# HackmodWear.net
KiCad netlist of a schematic drawn in EAGLE
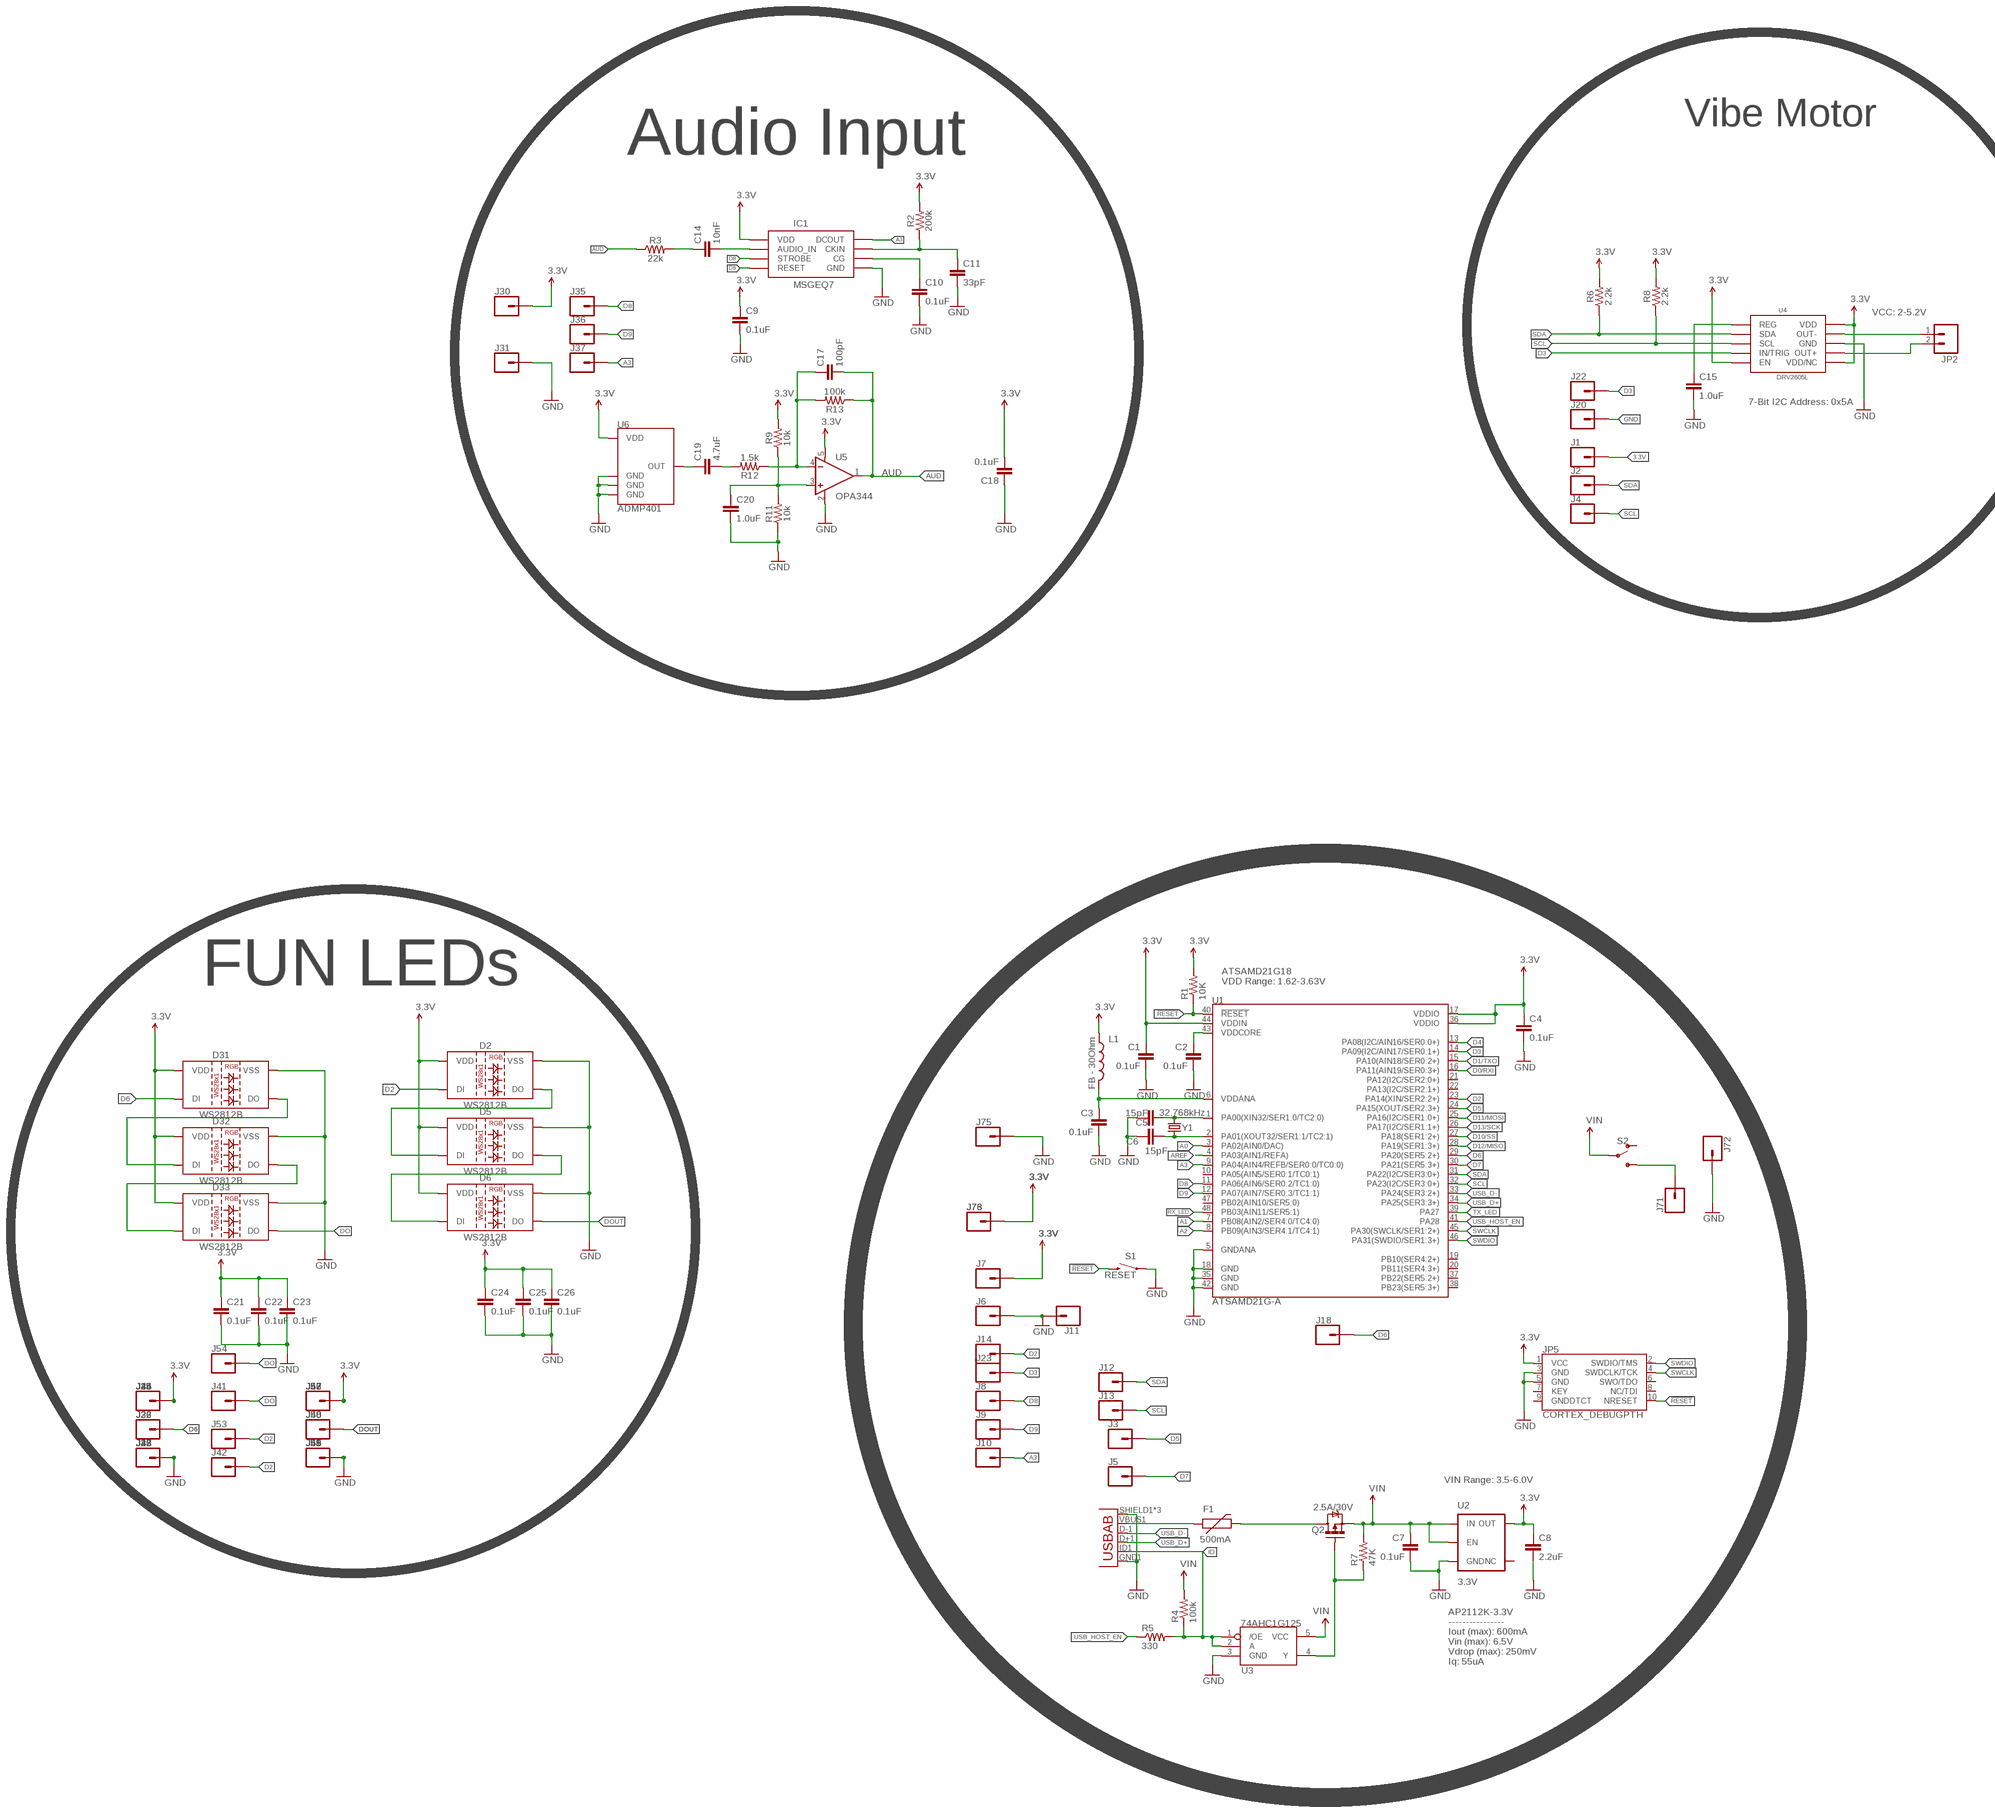
[diagram p0: schematic, sheet 1, part 1 of 3]
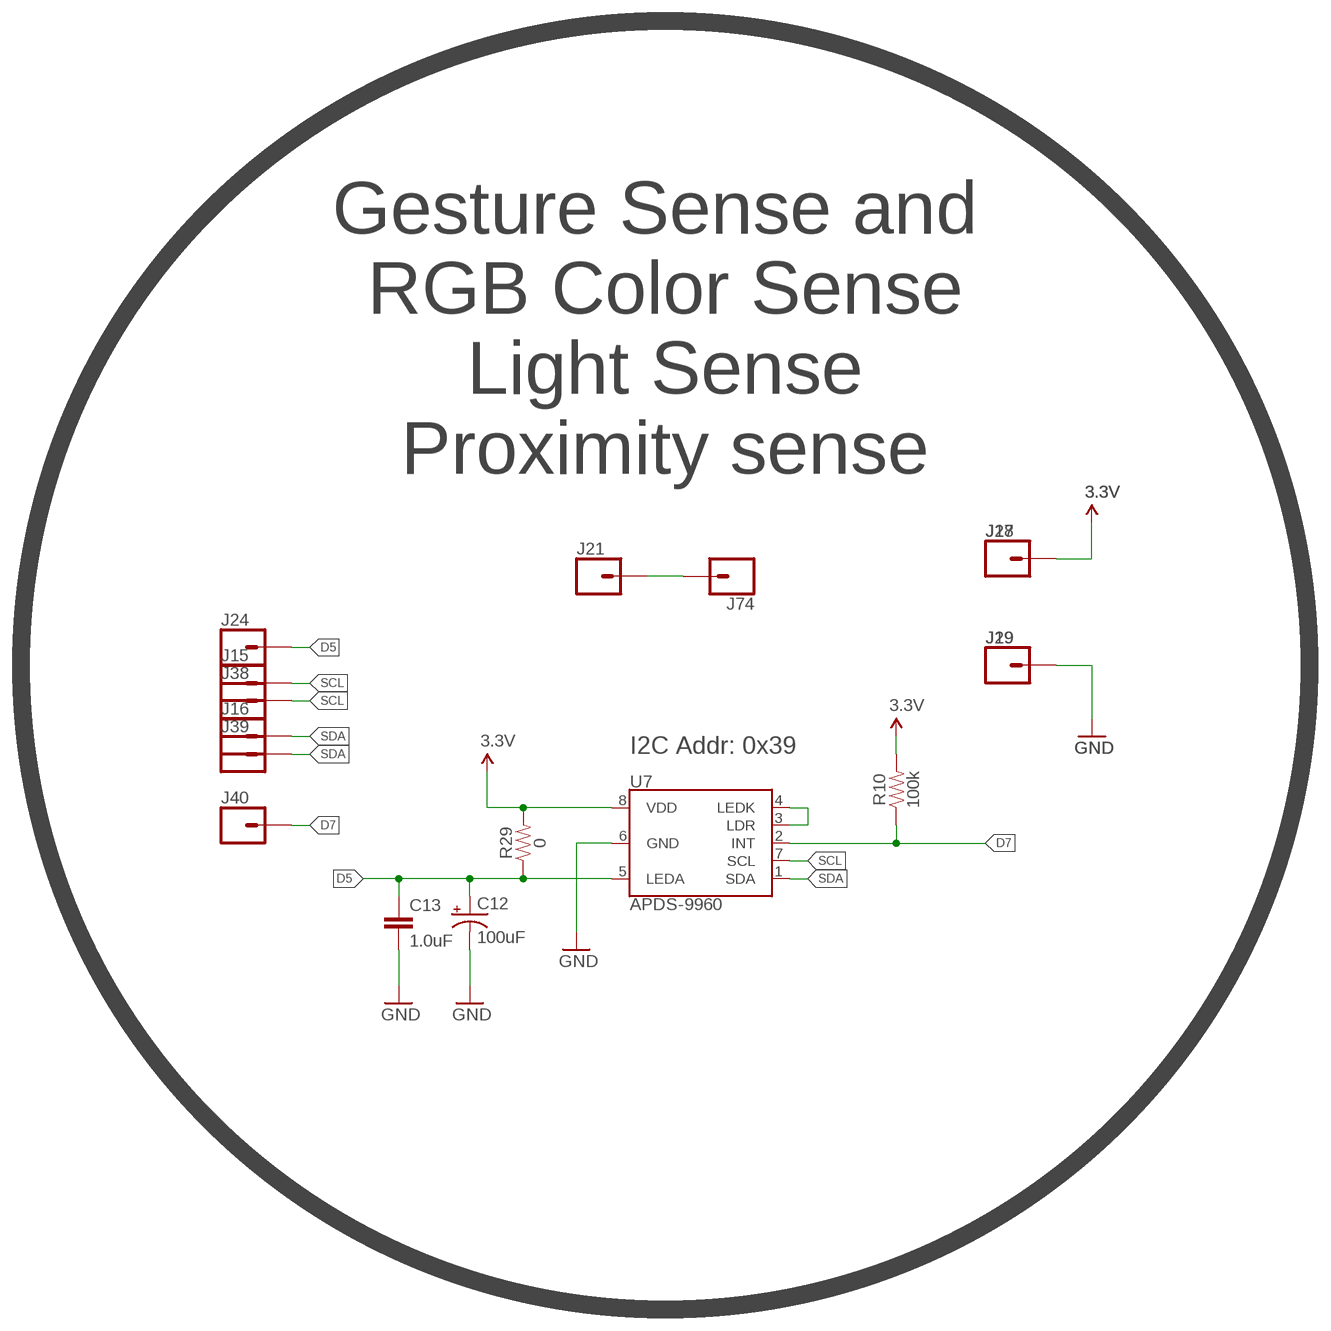
[diagram p1: schematic, sheet 1, part 2 of 3]
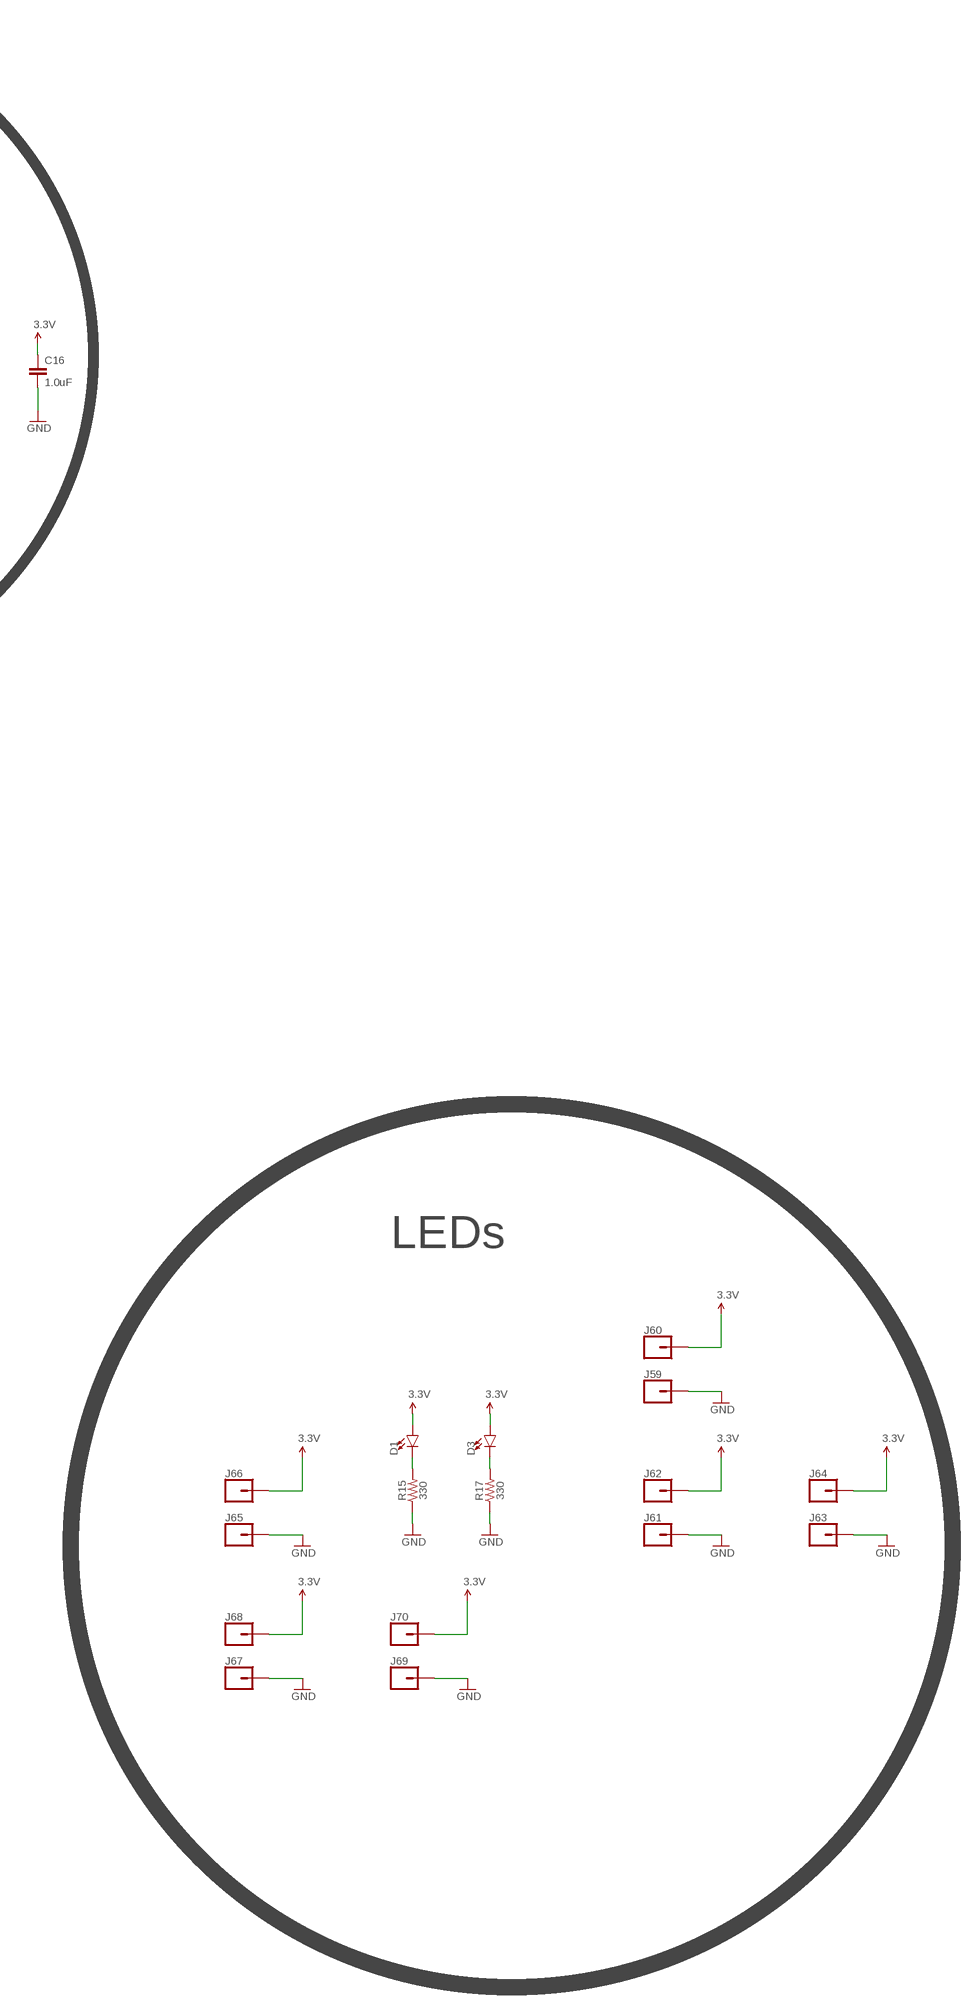
[diagram p2: schematic, sheet 1, part 3 of 3]

(export (version "E")
  (design (tool "Eeschema 10.0.6"))
  (components
    (comp (ref "C1")
      (value "0.1uF")
      (footprint "eagle-import:0603")
      (libsource (lib "eagle-import") (part "0.1UF-0603-25V-(+80/-20%)"))
    )
    (comp (ref "C2")
      (value "0.1uF")
      (footprint "eagle-import:0603")
      (libsource (lib "eagle-import") (part "0.1UF-0603-25V-(+80/-20%)"))
    )
    (comp (ref "C3")
      (value "0.1uF")
      (footprint "eagle-import:0603")
      (libsource (lib "eagle-import") (part "0.1UF-0603-25V-(+80/-20%)"))
    )
    (comp (ref "C4")
      (value "0.1uF")
      (footprint "eagle-import:0603")
      (libsource (lib "eagle-import") (part "0.1UF-0603-25V-(+80/-20%)"))
    )
    (comp (ref "C5")
      (value "15pF")
      (footprint "eagle-import:0603")
      (libsource (lib "eagle-import") (part "15PF-0603-50V-5%"))
    )
    (comp (ref "C6")
      (value "15pF")
      (footprint "eagle-import:0603")
      (libsource (lib "eagle-import") (part "15PF-0603-50V-5%"))
    )
    (comp (ref "C7")
      (value "0.1uF")
      (footprint "eagle-import:0603")
      (libsource (lib "eagle-import") (part "0.1UF-0603-25V-(+80/-20%)"))
    )
    (comp (ref "C8")
      (value "2.2uF")
      (footprint "eagle-import:0603-CAP")
      (libsource (lib "eagle-import") (part "2.2UF-10V-20%(0603)"))
    )
    (comp (ref "C9")
      (value "0.1uF")
      (footprint "eagle-import:0603")
      (libsource (lib "eagle-import") (part "0.1UF-0603-25V-(+80/-20%)"))
    )
    (comp (ref "C10")
      (value "0.1uF")
      (footprint "eagle-import:0603")
      (libsource (lib "eagle-import") (part "0.1UF-0603-25V-(+80/-20%)"))
    )
    (comp (ref "C11")
      (value "33pF")
      (footprint "eagle-import:0603")
      (libsource (lib "eagle-import") (part "33PF-0603-50V-5%"))
    )
    (comp (ref "C12")
      (value "100uF")
      (footprint "eagle-import:EIA7343")
      (libsource (lib "eagle-import") (part "100UF-POLAR-EIA7343-10V-10%(TANT)"))
    )
    (comp (ref "C13")
      (value "1.0uF")
      (footprint "eagle-import:0603")
      (libsource (lib "eagle-import") (part "1.0UF-0603-16V-10%"))
    )
    (comp (ref "C14")
      (value "10nF")
      (footprint "eagle-import:0603")
      (libsource (lib "eagle-import") (part "10NF-0603-50V-10%"))
    )
    (comp (ref "C15")
      (value "1.0uF")
      (footprint "eagle-import:0402-CAP")
      (libsource (lib "eagle-import") (part "1.0UF-16V-10%(0402)"))
    )
    (comp (ref "C16")
      (value "1.0uF")
      (footprint "eagle-import:0402-CAP")
      (libsource (lib "eagle-import") (part "1.0UF-16V-10%(0402)"))
    )
    (comp (ref "C17")
      (value "100pF")
      (footprint "eagle-import:0603")
      (libsource (lib "eagle-import") (part "100PF-0603-50V-5%"))
    )
    (comp (ref "C18")
      (value "0.1uF")
      (footprint "eagle-import:0603")
      (libsource (lib "eagle-import") (part "0.1UF-0603-25V-(+80/-20%)"))
    )
    (comp (ref "C19")
      (value "4.7uF")
      (footprint "eagle-import:0603")
      (libsource (lib "eagle-import") (part "4.7UF0603"))
    )
    (comp (ref "C20")
      (value "1.0uF")
      (footprint "eagle-import:0603")
      (libsource (lib "eagle-import") (part "1.0UF-0603-16V-10%"))
    )
    (comp (ref "C21")
      (value "0.1uF")
      (footprint "eagle-import:0603")
      (libsource (lib "eagle-import") (part "0.1UF-0603-25V-(+80/-20%)"))
    )
    (comp (ref "C22")
      (value "0.1uF")
      (footprint "eagle-import:0603")
      (libsource (lib "eagle-import") (part "0.1UF-0603-25V-(+80/-20%)"))
    )
    (comp (ref "C23")
      (value "0.1uF")
      (footprint "eagle-import:0603")
      (libsource (lib "eagle-import") (part "0.1UF-0603-25V-(+80/-20%)"))
    )
    (comp (ref "C24")
      (value "0.1uF")
      (footprint "eagle-import:0603")
      (libsource (lib "eagle-import") (part "0.1UF-0603-25V-(+80/-20%)"))
    )
    (comp (ref "C25")
      (value "0.1uF")
      (footprint "eagle-import:0603")
      (libsource (lib "eagle-import") (part "0.1UF-0603-25V-(+80/-20%)"))
    )
    (comp (ref "C26")
      (value "0.1uF")
      (footprint "eagle-import:0603")
      (libsource (lib "eagle-import") (part "0.1UF-0603-25V-(+80/-20%)"))
    )
    (comp (ref "D1")
      (value "LED1206")
      (footprint "eagle-import:LED-1206")
      (libsource (lib "eagle-import") (part "LED1206"))
    )
    (comp (ref "D2")
      (value "WS2812B")
      (footprint "eagle-import:WS2812B")
      (libsource (lib "eagle-import") (part "WS2812B"))
    )
    (comp (ref "D3")
      (value "LED1206")
      (footprint "eagle-import:LED-1206")
      (libsource (lib "eagle-import") (part "LED1206"))
    )
    (comp (ref "D5")
      (value "WS2812B")
      (footprint "eagle-import:WS2812B")
      (libsource (lib "eagle-import") (part "WS2812B"))
    )
    (comp (ref "D6")
      (value "WS2812B")
      (footprint "eagle-import:WS2812B")
      (libsource (lib "eagle-import") (part "WS2812B"))
    )
    (comp (ref "D31")
      (value "WS2812B")
      (footprint "eagle-import:WS2812B")
      (libsource (lib "eagle-import") (part "WS2812B"))
    )
    (comp (ref "D32")
      (value "WS2812B")
      (footprint "eagle-import:WS2812B")
      (libsource (lib "eagle-import") (part "WS2812B"))
    )
    (comp (ref "D33")
      (value "WS2812B")
      (footprint "eagle-import:WS2812B")
      (libsource (lib "eagle-import") (part "WS2812B"))
    )
    (comp (ref "F1")
      (value "500mA")
      (footprint "eagle-import:PTC-1206")
      (libsource (lib "eagle-import") (part "PTCSMD"))
    )
    (comp (ref "IC1")
      (value "MSGEQ7N")
      (footprint "eagle-import:SO08")
      (libsource (lib "eagle-import") (part "MSGEQ7SOIC"))
    )
    (comp (ref "J1")
      (value "CONN_01")
      (footprint "eagle-import:1X01")
      (libsource (lib "eagle-import") (part "CONN_01"))
    )
    (comp (ref "J2")
      (value "CONN_01")
      (footprint "eagle-import:1X01")
      (libsource (lib "eagle-import") (part "CONN_01"))
    )
    (comp (ref "J3")
      (value "CONN_01")
      (footprint "eagle-import:1X01")
      (libsource (lib "eagle-import") (part "CONN_01"))
    )
    (comp (ref "J4")
      (value "CONN_01")
      (footprint "eagle-import:1X01")
      (libsource (lib "eagle-import") (part "CONN_01"))
    )
    (comp (ref "J5")
      (value "CONN_01")
      (footprint "eagle-import:1X01")
      (libsource (lib "eagle-import") (part "CONN_01"))
    )
    (comp (ref "J6")
      (value "CONN_01")
      (footprint "eagle-import:1X01")
      (libsource (lib "eagle-import") (part "CONN_01"))
    )
    (comp (ref "J7")
      (value "CONN_01")
      (footprint "eagle-import:1X01")
      (libsource (lib "eagle-import") (part "CONN_01"))
    )
    (comp (ref "J8")
      (value "CONN_01")
      (footprint "eagle-import:1X01")
      (libsource (lib "eagle-import") (part "CONN_01"))
    )
    (comp (ref "J9")
      (value "CONN_01")
      (footprint "eagle-import:1X01")
      (libsource (lib "eagle-import") (part "CONN_01"))
    )
    (comp (ref "J10")
      (value "CONN_01")
      (footprint "eagle-import:1X01")
      (libsource (lib "eagle-import") (part "CONN_01"))
    )
    (comp (ref "J11")
      (value "CONN_01")
      (footprint "eagle-import:1X01")
      (libsource (lib "eagle-import") (part "CONN_01"))
    )
    (comp (ref "J12")
      (value "CONN_01")
      (footprint "eagle-import:1X01")
      (libsource (lib "eagle-import") (part "CONN_01"))
    )
    (comp (ref "J13")
      (value "CONN_01")
      (footprint "eagle-import:1X01")
      (libsource (lib "eagle-import") (part "CONN_01"))
    )
    (comp (ref "J14")
      (value "CONN_01")
      (footprint "eagle-import:1X01")
      (libsource (lib "eagle-import") (part "CONN_01"))
    )
    (comp (ref "J15")
      (value "CONN_01")
      (footprint "eagle-import:1X01")
      (libsource (lib "eagle-import") (part "CONN_01"))
    )
    (comp (ref "J16")
      (value "CONN_01")
      (footprint "eagle-import:1X01")
      (libsource (lib "eagle-import") (part "CONN_01"))
    )
    (comp (ref "J17")
      (value "CONN_01")
      (footprint "eagle-import:1X01")
      (libsource (lib "eagle-import") (part "CONN_01"))
    )
    (comp (ref "J18")
      (value "CONN_01")
      (footprint "eagle-import:1X01")
      (libsource (lib "eagle-import") (part "CONN_01"))
    )
    (comp (ref "J19")
      (value "CONN_01")
      (footprint "eagle-import:1X01")
      (libsource (lib "eagle-import") (part "CONN_01"))
    )
    (comp (ref "J20")
      (value "CONN_01")
      (footprint "eagle-import:1X01")
      (libsource (lib "eagle-import") (part "CONN_01"))
    )
    (comp (ref "J21")
      (value "CONN_01")
      (footprint "eagle-import:1X01")
      (libsource (lib "eagle-import") (part "CONN_01"))
    )
    (comp (ref "J22")
      (value "CONN_01")
      (footprint "eagle-import:1X01")
      (libsource (lib "eagle-import") (part "CONN_01"))
    )
    (comp (ref "J23")
      (value "CONN_01")
      (footprint "eagle-import:1X01")
      (libsource (lib "eagle-import") (part "CONN_01"))
    )
    (comp (ref "J24")
      (value "CONN_01")
      (footprint "eagle-import:1X01")
      (libsource (lib "eagle-import") (part "CONN_01"))
    )
    (comp (ref "J25")
      (value "CONN_01")
      (footprint "eagle-import:1X01")
      (libsource (lib "eagle-import") (part "CONN_01"))
    )
    (comp (ref "J26")
      (value "CONN_01")
      (footprint "eagle-import:1X01")
      (libsource (lib "eagle-import") (part "CONN_01"))
    )
    (comp (ref "J27")
      (value "CONN_01")
      (footprint "eagle-import:1X01")
      (libsource (lib "eagle-import") (part "CONN_01"))
    )
    (comp (ref "J28")
      (value "CONN_01")
      (footprint "eagle-import:1X01")
      (libsource (lib "eagle-import") (part "CONN_01"))
    )
    (comp (ref "J29")
      (value "CONN_01")
      (footprint "eagle-import:1X01")
      (libsource (lib "eagle-import") (part "CONN_01"))
    )
    (comp (ref "J30")
      (value "CONN_01")
      (footprint "eagle-import:1X01")
      (libsource (lib "eagle-import") (part "CONN_01"))
    )
    (comp (ref "J31")
      (value "CONN_01")
      (footprint "eagle-import:1X01")
      (libsource (lib "eagle-import") (part "CONN_01"))
    )
    (comp (ref "J32")
      (value "CONN_01")
      (footprint "eagle-import:1X01")
      (libsource (lib "eagle-import") (part "CONN_01"))
    )
    (comp (ref "J33")
      (value "CONN_01")
      (footprint "eagle-import:1X01")
      (libsource (lib "eagle-import") (part "CONN_01"))
    )
    (comp (ref "J34")
      (value "CONN_01")
      (footprint "eagle-import:1X01")
      (libsource (lib "eagle-import") (part "CONN_01"))
    )
    (comp (ref "J35")
      (value "CONN_01")
      (footprint "eagle-import:1X01")
      (libsource (lib "eagle-import") (part "CONN_01"))
    )
    (comp (ref "J36")
      (value "CONN_01")
      (footprint "eagle-import:1X01")
      (libsource (lib "eagle-import") (part "CONN_01"))
    )
    (comp (ref "J37")
      (value "CONN_01")
      (footprint "eagle-import:1X01")
      (libsource (lib "eagle-import") (part "CONN_01"))
    )
    (comp (ref "J38")
      (value "CONN_01")
      (footprint "eagle-import:1X01")
      (libsource (lib "eagle-import") (part "CONN_01"))
    )
    (comp (ref "J39")
      (value "CONN_01")
      (footprint "eagle-import:1X01")
      (libsource (lib "eagle-import") (part "CONN_01"))
    )
    (comp (ref "J40")
      (value "CONN_01")
      (footprint "eagle-import:1X01")
      (libsource (lib "eagle-import") (part "CONN_01"))
    )
    (comp (ref "J41")
      (value "CONN_01")
      (footprint "eagle-import:1X01")
      (libsource (lib "eagle-import") (part "CONN_01"))
    )
    (comp (ref "J42")
      (value "CONN_01")
      (footprint "eagle-import:1X01")
      (libsource (lib "eagle-import") (part "CONN_01"))
    )
    (comp (ref "J43")
      (value "CONN_01")
      (footprint "eagle-import:1X01")
      (libsource (lib "eagle-import") (part "CONN_01"))
    )
    (comp (ref "J44")
      (value "CONN_01")
      (footprint "eagle-import:1X01")
      (libsource (lib "eagle-import") (part "CONN_01"))
    )
    (comp (ref "J45")
      (value "CONN_01")
      (footprint "eagle-import:1X01")
      (libsource (lib "eagle-import") (part "CONN_01"))
    )
    (comp (ref "J46")
      (value "CONN_01")
      (footprint "eagle-import:1X01")
      (libsource (lib "eagle-import") (part "CONN_01"))
    )
    (comp (ref "J47")
      (value "CONN_01")
      (footprint "eagle-import:1X01")
      (libsource (lib "eagle-import") (part "CONN_01"))
    )
    (comp (ref "J48")
      (value "CONN_01")
      (footprint "eagle-import:1X01")
      (libsource (lib "eagle-import") (part "CONN_01"))
    )
    (comp (ref "J49")
      (value "CONN_01")
      (footprint "eagle-import:1X01")
      (libsource (lib "eagle-import") (part "CONN_01"))
    )
    (comp (ref "J50")
      (value "CONN_01")
      (footprint "eagle-import:1X01")
      (libsource (lib "eagle-import") (part "CONN_01"))
    )
    (comp (ref "J51")
      (value "CONN_01")
      (footprint "eagle-import:1X01")
      (libsource (lib "eagle-import") (part "CONN_01"))
    )
    (comp (ref "J52")
      (value "CONN_01")
      (footprint "eagle-import:1X01")
      (libsource (lib "eagle-import") (part "CONN_01"))
    )
    (comp (ref "J53")
      (value "CONN_01")
      (footprint "eagle-import:1X01")
      (libsource (lib "eagle-import") (part "CONN_01"))
    )
    (comp (ref "J54")
      (value "CONN_01")
      (footprint "eagle-import:1X01")
      (libsource (lib "eagle-import") (part "CONN_01"))
    )
    (comp (ref "J55")
      (value "CONN_01")
      (footprint "eagle-import:1X01")
      (libsource (lib "eagle-import") (part "CONN_01"))
    )
    (comp (ref "J56")
      (value "CONN_01")
      (footprint "eagle-import:1X01")
      (libsource (lib "eagle-import") (part "CONN_01"))
    )
    (comp (ref "J57")
      (value "CONN_01")
      (footprint "eagle-import:1X01")
      (libsource (lib "eagle-import") (part "CONN_01"))
    )
    (comp (ref "J58")
      (value "CONN_01")
      (footprint "eagle-import:1X01")
      (libsource (lib "eagle-import") (part "CONN_01"))
    )
    (comp (ref "J59")
      (value "CONN_01")
      (footprint "eagle-import:1X01")
      (libsource (lib "eagle-import") (part "CONN_01"))
    )
    (comp (ref "J60")
      (value "CONN_01")
      (footprint "eagle-import:1X01")
      (libsource (lib "eagle-import") (part "CONN_01"))
    )
    (comp (ref "J61")
      (value "CONN_01")
      (footprint "eagle-import:1X01")
      (libsource (lib "eagle-import") (part "CONN_01"))
    )
    (comp (ref "J62")
      (value "CONN_01")
      (footprint "eagle-import:1X01")
      (libsource (lib "eagle-import") (part "CONN_01"))
    )
    (comp (ref "J63")
      (value "CONN_01")
      (footprint "eagle-import:1X01")
      (libsource (lib "eagle-import") (part "CONN_01"))
    )
    (comp (ref "J64")
      (value "CONN_01")
      (footprint "eagle-import:1X01")
      (libsource (lib "eagle-import") (part "CONN_01"))
    )
    (comp (ref "J65")
      (value "CONN_01")
      (footprint "eagle-import:1X01")
      (libsource (lib "eagle-import") (part "CONN_01"))
    )
    (comp (ref "J66")
      (value "CONN_01")
      (footprint "eagle-import:1X01")
      (libsource (lib "eagle-import") (part "CONN_01"))
    )
    (comp (ref "J67")
      (value "CONN_01")
      (footprint "eagle-import:1X01")
      (libsource (lib "eagle-import") (part "CONN_01"))
    )
    (comp (ref "J68")
      (value "CONN_01")
      (footprint "eagle-import:1X01")
      (libsource (lib "eagle-import") (part "CONN_01"))
    )
    (comp (ref "J69")
      (value "CONN_01")
      (footprint "eagle-import:1X01")
      (libsource (lib "eagle-import") (part "CONN_01"))
    )
    (comp (ref "J70")
      (value "CONN_01")
      (footprint "eagle-import:1X01")
      (libsource (lib "eagle-import") (part "CONN_01"))
    )
    (comp (ref "J71")
      (value "CONN_01")
      (footprint "eagle-import:1X01")
      (libsource (lib "eagle-import") (part "CONN_01"))
    )
    (comp (ref "J72")
      (value "CONN_01")
      (footprint "eagle-import:1X01")
      (libsource (lib "eagle-import") (part "CONN_01"))
    )
    (comp (ref "J73")
      (value "CONN_01")
      (footprint "eagle-import:1X01")
      (libsource (lib "eagle-import") (part "CONN_01"))
    )
    (comp (ref "J74")
      (value "CONN_01")
      (footprint "eagle-import:1X01")
      (libsource (lib "eagle-import") (part "CONN_01"))
    )
    (comp (ref "J75")
      (value "CONN_01")
      (footprint "eagle-import:1X01")
      (libsource (lib "eagle-import") (part "CONN_01"))
    )
    (comp (ref "J76")
      (value "CONN_01")
      (footprint "eagle-import:1X01")
      (libsource (lib "eagle-import") (part "CONN_01"))
    )
    (comp (ref "JP2")
      (value "M02PTH")
      (footprint "eagle-import:1X02@1")
      (libsource (lib "eagle-import") (part "M02PTH"))
    )
    (comp (ref "JP3")
      (value "USB-ABCONN-11794")
      (footprint "eagle-import:USB-AB-MICRO-SMD_V03")
      (libsource (lib "eagle-import") (part "USB-ABCONN-11794"))
    )
    (comp (ref "JP5")
      (value "CORTEX_DEBUGPTH")
      (footprint "eagle-import:2X5-PTH-1.27MM")
      (libsource (lib "eagle-import") (part "CORTEX_DEBUGPTH"))
    )
    (comp (ref "L1")
      (value "FB - 30Ohm")
      (footprint "eagle-import:0603")
      (libsource (lib "eagle-import") (part "INDUCTOR0603"))
    )
    (comp (ref "Q2")
      (value "2.5A/30V")
      (footprint "eagle-import:SOT23-3")
      (libsource (lib "eagle-import") (part "MOSFET-PCHANNELDMG2307L"))
    )
    (comp (ref "R1")
      (value "10K")
      (footprint "eagle-import:0603-RES@1")
      (libsource (lib "eagle-import") (part "10KOHM-1/10W-1%(0603)0603"))
    )
    (comp (ref "R2")
      (value "200k")
      (footprint "eagle-import:0603")
      (libsource (lib "eagle-import") (part "200KOHM-0603-1/10W-1%"))
    )
    (comp (ref "R3")
      (value "22k")
      (footprint "eagle-import:0603")
      (libsource (lib "eagle-import") (part "22KOHM-0603-1/10W-1%"))
    )
    (comp (ref "R4")
      (value "100k")
      (footprint "eagle-import:0603-RES@1")
      (libsource (lib "eagle-import") (part "100KOHM-1/10W-1%(0603)"))
    )
    (comp (ref "R5")
      (value "330")
      (footprint "eagle-import:0603-RES@1")
      (libsource (lib "eagle-import") (part "330OHM1/10W1%(0603)"))
    )
    (comp (ref "R6")
      (value "2.2k")
      (footprint "eagle-import:0603")
      (libsource (lib "eagle-import") (part "2.2KOHM-0603-1/10W-1%"))
    )
    (comp (ref "R7")
      (value "47K")
      (footprint "eagle-import:0603-RES@1")
      (libsource (lib "eagle-import") (part "47KOHM1/10W1%(0603)"))
    )
    (comp (ref "R8")
      (value "2.2k")
      (footprint "eagle-import:0603")
      (libsource (lib "eagle-import") (part "2.2KOHM-0603-1/10W-1%"))
    )
    (comp (ref "R9")
      (value "10k")
      (footprint "eagle-import:0603")
      (libsource (lib "eagle-import") (part "10KOHM-0603-1/10W-1%"))
    )
    (comp (ref "R10")
      (value "100k")
      (footprint "eagle-import:0603")
      (libsource (lib "eagle-import") (part "100KOHM-0603-1/10W-1%"))
    )
    (comp (ref "R11")
      (value "10k")
      (footprint "eagle-import:0603")
      (libsource (lib "eagle-import") (part "10KOHM-0603-1/10W-1%"))
    )
    (comp (ref "R12")
      (value "1.5k")
      (footprint "eagle-import:0603")
      (libsource (lib "eagle-import") (part "1.5KOHM-0603-1/10W-1%"))
    )
    (comp (ref "R13")
      (value "100k")
      (footprint "eagle-import:0603")
      (libsource (lib "eagle-import") (part "100KOHM-0603-1/10W-1%"))
    )
    (comp (ref "R15")
      (value "330")
      (footprint "eagle-import:0603")
      (libsource (lib "eagle-import") (part "330OHM-0603-1/10W-1%"))
    )
    (comp (ref "R17")
      (value "330")
      (footprint "eagle-import:0603")
      (libsource (lib "eagle-import") (part "330OHM-0603-1/10W-1%"))
    )
    (comp (ref "R29")
      (value "0")
      (footprint "eagle-import:0603")
      (libsource (lib "eagle-import") (part "0OHM-0603-1/10W-5%"))
    )
    (comp (ref "S1")
      (value "RESET")
      (footprint "eagle-import:TACTILE_SWITCH_SMD_4.6X2.8MM")
      (libsource (lib "eagle-import") (part "SWITCH-MOMENTARY-2SMD-4.6X2.8MM"))
    )
    (comp (ref "S2")
      (value "SWITCH-SPDT-SMD-RIGHT-ANGLE")
      (footprint "eagle-import:SWITCH_SPST_SMD_A")
      (libsource (lib "eagle-import") (part "SWITCH-SPDT-SMD-RIGHT-ANGLE"))
    )
    (comp (ref "U1")
      (value "ATSAMD21G-A")
      (footprint "eagle-import:TQFP-48")
      (libsource (lib "eagle-import") (part "ATSAMD21G-A"))
    )
    (comp (ref "U2")
      (value "3.3V")
      (footprint "eagle-import:SOT23-5")
      (libsource (lib "eagle-import") (part "V_REG_AP2112K-3.3V"))
    )
    (comp (ref "U3")
      (value "74AHC1G125")
      (footprint "eagle-import:SOT23-5")
      (libsource (lib "eagle-import") (part "74AHC1G125"))
    )
    (comp (ref "U4")
      (value "DRV2605L")
      (footprint "eagle-import:VSSOP-10")
      (libsource (lib "eagle-import") (part "DRV2605L"))
    )
    (comp (ref "U5")
      (value "OPA344")
      (footprint "eagle-import:SOT23-5")
      (libsource (lib "eagle-import") (part "OPA344"))
    )
    (comp (ref "U6")
      (value "ADMP401")
      (footprint "eagle-import:ADMP401")
      (libsource (lib "eagle-import") (part "ADMP401"))
    )
    (comp (ref "U7")
      (value "APDS-9960")
      (footprint "eagle-import:APDS-9960")
      (libsource (lib "eagle-import") (part "APDS-9960"))
    )
    (comp (ref "Y1")
      (value "32.768kHz")
      (footprint "eagle-import:CRYSTAL-SMD-3.2X1.5MM")
      (libsource (lib "eagle-import") (part "CRYSTAL3.2X1.5MM"))
    )
  )
  (nets
    (net (code "1") (name "/~{RESET}") (class "Default")
      (node (ref "JP5") (pin "10") (pinfunction "NRESET_10") (pintype "bidirectional"))
      (node (ref "R1") (pin "1") (pinfunction "1_1") (pintype "passive"))
      (node (ref "S1") (pin "3") (pinfunction "2_3") (pintype "passive"))
      (node (ref "S1") (pin "4") (pinfunction "2_4") (pintype "passive"))
      (node (ref "U1") (pin "40") (pinfunction "~{RESET}_40") (pintype "bidirectional"))
    )
    (net (code "2") (name "3.3V") (class "Default")
      (node (ref "C1") (pin "1") (pinfunction "1_1") (pintype "passive"))
      (node (ref "C16") (pin "1") (pinfunction "1_1") (pintype "passive"))
      (node (ref "C18") (pin "2") (pinfunction "2_2") (pintype "passive"))
      (node (ref "C21") (pin "1") (pinfunction "1_1") (pintype "passive"))
      (node (ref "C22") (pin "1") (pinfunction "1_1") (pintype "passive"))
      (node (ref "C23") (pin "1") (pinfunction "1_1") (pintype "passive"))
      (node (ref "C24") (pin "1") (pinfunction "1_1") (pintype "passive"))
      (node (ref "C25") (pin "1") (pinfunction "1_1") (pintype "passive"))
      (node (ref "C26") (pin "1") (pinfunction "1_1") (pintype "passive"))
      (node (ref "C4") (pin "1") (pinfunction "1_1") (pintype "passive"))
      (node (ref "C8") (pin "1") (pinfunction "1_1") (pintype "passive"))
      (node (ref "C9") (pin "1") (pinfunction "1_1") (pintype "passive"))
      (node (ref "D1") (pin "A") (pinfunction "A_A") (pintype "passive"))
      (node (ref "D2") (pin "1") (pinfunction "VDD_1") (pintype "bidirectional"))
      (node (ref "D3") (pin "A") (pinfunction "A_A") (pintype "passive"))
      (node (ref "D31") (pin "1") (pinfunction "VDD_1") (pintype "bidirectional"))
      (node (ref "D32") (pin "1") (pinfunction "VDD_1") (pintype "bidirectional"))
      (node (ref "D33") (pin "1") (pinfunction "VDD_1") (pintype "bidirectional"))
      (node (ref "D5") (pin "1") (pinfunction "VDD_1") (pintype "bidirectional"))
      (node (ref "D6") (pin "1") (pinfunction "VDD_1") (pintype "bidirectional"))
      (node (ref "IC1") (pin "1") (pinfunction "VDD_1") (pintype "input"))
      (node (ref "J1") (pin "P$1") (pinfunction "1_P$1") (pintype "passive"))
      (node (ref "J17") (pin "P$1") (pinfunction "1_P$1") (pintype "passive"))
      (node (ref "J25") (pin "P$1") (pinfunction "1_P$1") (pintype "passive"))
      (node (ref "J28") (pin "P$1") (pinfunction "1_P$1") (pintype "passive"))
      (node (ref "J30") (pin "P$1") (pinfunction "1_P$1") (pintype "passive"))
      (node (ref "J34") (pin "P$1") (pinfunction "1_P$1") (pintype "passive"))
      (node (ref "J44") (pin "P$1") (pinfunction "1_P$1") (pintype "passive"))
      (node (ref "J45") (pin "P$1") (pinfunction "1_P$1") (pintype "passive"))
      (node (ref "J47") (pin "P$1") (pinfunction "1_P$1") (pintype "passive"))
      (node (ref "J52") (pin "P$1") (pinfunction "1_P$1") (pintype "passive"))
      (node (ref "J56") (pin "P$1") (pinfunction "1_P$1") (pintype "passive"))
      (node (ref "J57") (pin "P$1") (pinfunction "1_P$1") (pintype "passive"))
      (node (ref "J60") (pin "P$1") (pinfunction "1_P$1") (pintype "passive"))
      (node (ref "J62") (pin "P$1") (pinfunction "1_P$1") (pintype "passive"))
      (node (ref "J64") (pin "P$1") (pinfunction "1_P$1") (pintype "passive"))
      (node (ref "J66") (pin "P$1") (pinfunction "1_P$1") (pintype "passive"))
      (node (ref "J68") (pin "P$1") (pinfunction "1_P$1") (pintype "passive"))
      (node (ref "J7") (pin "P$1") (pinfunction "1_P$1") (pintype "passive"))
      (node (ref "J70") (pin "P$1") (pinfunction "1_P$1") (pintype "passive"))
      (node (ref "J73") (pin "P$1") (pinfunction "1_P$1") (pintype "passive"))
      (node (ref "J76") (pin "P$1") (pinfunction "1_P$1") (pintype "passive"))
      (node (ref "JP5") (pin "1") (pinfunction "VCC_1") (pintype "bidirectional"))
      (node (ref "L1") (pin "1") (pinfunction "1_1") (pintype "passive"))
      (node (ref "R1") (pin "2") (pinfunction "2_2") (pintype "passive"))
      (node (ref "R10") (pin "2") (pinfunction "2_2") (pintype "passive"))
      (node (ref "R2") (pin "2") (pinfunction "2_2") (pintype "passive"))
      (node (ref "R29") (pin "2") (pinfunction "2_2") (pintype "passive"))
      (node (ref "R6") (pin "2") (pinfunction "2_2") (pintype "passive"))
      (node (ref "R8") (pin "2") (pinfunction "2_2") (pintype "passive"))
      (node (ref "R9") (pin "2") (pinfunction "2_2") (pintype "passive"))
      (node (ref "U1") (pin "17") (pinfunction "VDDIO_17") (pintype "bidirectional"))
      (node (ref "U1") (pin "36") (pinfunction "VDDIO_36") (pintype "bidirectional"))
      (node (ref "U1") (pin "44") (pinfunction "VDDIN_44") (pintype "bidirectional"))
      (node (ref "U2") (pin "5") (pinfunction "OUT_5") (pintype "passive"))
      (node (ref "U4") (pin "P$10") (pinfunction "VDD_P$10") (pintype "bidirectional"))
      (node (ref "U4") (pin "P$5") (pinfunction "EN_P$5") (pintype "bidirectional"))
      (node (ref "U4") (pin "P$6") (pinfunction "VDD/NC_P$6") (pintype "bidirectional"))
      (node (ref "U5") (pin "5") (pinfunction "V+_5") (pintype "power_in"))
      (node (ref "U6") (pin "5") (pinfunction "VDD_5") (pintype "bidirectional"))
      (node (ref "U7") (pin "8") (pinfunction "VDD_8") (pintype "bidirectional"))
    )
    (net (code "3") (name "A0") (class "Default")
      (node (ref "U1") (pin "3") (pinfunction "PA02(AIN0/DAC)_3") (pintype "bidirectional"))
    )
    (net (code "4") (name "A1") (class "Default")
      (node (ref "U1") (pin "7") (pinfunction "PB08(AIN2/SER4:0/TC4:0)_7") (pintype "bidirectional"))
    )
    (net (code "5") (name "A2") (class "Default")
      (node (ref "U1") (pin "8") (pinfunction "PB09(AIN3/SER4:1/TC4:1)_8") (pintype "bidirectional"))
    )
    (net (code "6") (name "A3") (class "Default")
      (node (ref "IC1") (pin "3") (pinfunction "DCOUT_3") (pintype "bidirectional"))
      (node (ref "J10") (pin "P$1") (pinfunction "1_P$1") (pintype "passive"))
      (node (ref "J37") (pin "P$1") (pinfunction "1_P$1") (pintype "passive"))
      (node (ref "U1") (pin "9") (pinfunction "PA04(AIN4/REFB/SER0:0/TC0:0)_9") (pintype "bidirectional"))
    )
    (net (code "7") (name "AREF") (class "Default")
      (node (ref "U1") (pin "4") (pinfunction "PA03(AIN1/REFA)_4") (pintype "bidirectional"))
    )
    (net (code "8") (name "AUD") (class "Default")
      (node (ref "C17") (pin "2") (pinfunction "2_2") (pintype "passive"))
      (node (ref "R13") (pin "1") (pinfunction "1_1") (pintype "passive"))
      (node (ref "R3") (pin "1") (pinfunction "1_1") (pintype "passive"))
      (node (ref "U5") (pin "1") (pinfunction "OUT_1") (pintype "output"))
    )
    (net (code "9") (name "D0{slash}RXI") (class "Default")
      (node (ref "U1") (pin "16") (pinfunction "PA11(AIN19/SER0:3+)_16") (pintype "bidirectional"))
    )
    (net (code "10") (name "D1{slash}TXO") (class "Default")
      (node (ref "U1") (pin "15") (pinfunction "PA10(AIN18/SER0:2+)_15") (pintype "bidirectional"))
    )
    (net (code "11") (name "D2") (class "Default")
      (node (ref "D2") (pin "4") (pinfunction "DI_4") (pintype "bidirectional"))
      (node (ref "J14") (pin "P$1") (pinfunction "1_P$1") (pintype "passive"))
      (node (ref "J42") (pin "P$1") (pinfunction "1_P$1") (pintype "passive"))
      (node (ref "J53") (pin "P$1") (pinfunction "1_P$1") (pintype "passive"))
      (node (ref "U1") (pin "23") (pinfunction "PA14(XIN/SER2:2+)_23") (pintype "bidirectional"))
    )
    (net (code "12") (name "D3") (class "Default")
      (node (ref "J22") (pin "P$1") (pinfunction "1_P$1") (pintype "passive"))
      (node (ref "J23") (pin "P$1") (pinfunction "1_P$1") (pintype "passive"))
      (node (ref "U1") (pin "14") (pinfunction "PA09(I2C/AIN17/SER0:1+)_14") (pintype "bidirectional"))
      (node (ref "U4") (pin "P$4") (pinfunction "IN/TRIG_P$4") (pintype "bidirectional"))
    )
    (net (code "13") (name "D4") (class "Default")
      (node (ref "U1") (pin "13") (pinfunction "PA08(I2C/AIN16/SER0:0+)_13") (pintype "bidirectional"))
    )
    (net (code "14") (name "D5") (class "Default")
      (node (ref "C12") (pin "A") (pinfunction "+_A") (pintype "passive"))
      (node (ref "C13") (pin "1") (pinfunction "1_1") (pintype "passive"))
      (node (ref "J24") (pin "P$1") (pinfunction "1_P$1") (pintype "passive"))
      (node (ref "J3") (pin "P$1") (pinfunction "1_P$1") (pintype "passive"))
      (node (ref "R29") (pin "1") (pinfunction "1_1") (pintype "passive"))
      (node (ref "U1") (pin "24") (pinfunction "PA15(XOUT/SER2:3+)_24") (pintype "bidirectional"))
      (node (ref "U7") (pin "5") (pinfunction "LEDA_5") (pintype "bidirectional"))
    )
    (net (code "15") (name "D6") (class "Default")
      (node (ref "D31") (pin "4") (pinfunction "DI_4") (pintype "bidirectional"))
      (node (ref "J18") (pin "P$1") (pinfunction "1_P$1") (pintype "passive"))
      (node (ref "J26") (pin "P$1") (pinfunction "1_P$1") (pintype "passive"))
      (node (ref "J32") (pin "P$1") (pinfunction "1_P$1") (pintype "passive"))
      (node (ref "U1") (pin "29") (pinfunction "PA20(SER5:2+)_29") (pintype "bidirectional"))
    )
    (net (code "16") (name "D7") (class "Default")
      (node (ref "J40") (pin "P$1") (pinfunction "1_P$1") (pintype "passive"))
      (node (ref "J5") (pin "P$1") (pinfunction "1_P$1") (pintype "passive"))
      (node (ref "R10") (pin "1") (pinfunction "1_1") (pintype "passive"))
      (node (ref "U1") (pin "30") (pinfunction "PA21(SER5:3+)_30") (pintype "bidirectional"))
      (node (ref "U7") (pin "2") (pinfunction "INT_2") (pintype "bidirectional"))
    )
    (net (code "17") (name "D8") (class "Default")
      (node (ref "IC1") (pin "4") (pinfunction "STROBE_4") (pintype "input"))
      (node (ref "J35") (pin "P$1") (pinfunction "1_P$1") (pintype "passive"))
      (node (ref "J8") (pin "P$1") (pinfunction "1_P$1") (pintype "passive"))
      (node (ref "U1") (pin "11") (pinfunction "PA06(AIN6/SER0:2/TC1:0)_11") (pintype "bidirectional"))
    )
    (net (code "18") (name "D9") (class "Default")
      (node (ref "IC1") (pin "7") (pinfunction "RESET_7") (pintype "input"))
      (node (ref "J36") (pin "P$1") (pinfunction "1_P$1") (pintype "passive"))
      (node (ref "J9") (pin "P$1") (pinfunction "1_P$1") (pintype "passive"))
      (node (ref "U1") (pin "12") (pinfunction "PA07(AIN7/SER0:3/TC1:1)_12") (pintype "bidirectional"))
    )
    (net (code "19") (name "D10{slash}SS") (class "Default")
      (node (ref "U1") (pin "27") (pinfunction "PA18(SER1:2+)_27") (pintype "bidirectional"))
    )
    (net (code "20") (name "D11{slash}MOSI") (class "Default")
      (node (ref "U1") (pin "25") (pinfunction "PA16(I2C/SER1:0+)_25") (pintype "bidirectional"))
    )
    (net (code "21") (name "D12{slash}MISO") (class "Default")
      (node (ref "U1") (pin "28") (pinfunction "PA19(SER1:3+)_28") (pintype "bidirectional"))
    )
    (net (code "22") (name "D13{slash}SCK") (class "Default")
      (node (ref "U1") (pin "26") (pinfunction "PA17(I2C/SER1:1+)_26") (pintype "bidirectional"))
    )
    (net (code "23") (name "DO") (class "Default")
      (node (ref "D33") (pin "2") (pinfunction "DO_2") (pintype "bidirectional"))
      (node (ref "J41") (pin "P$1") (pinfunction "1_P$1") (pintype "passive"))
      (node (ref "J54") (pin "P$1") (pinfunction "1_P$1") (pintype "passive"))
    )
    (net (code "24") (name "DOUT") (class "Default")
      (node (ref "D6") (pin "2") (pinfunction "DO_2") (pintype "bidirectional"))
      (node (ref "J48") (pin "P$1") (pinfunction "1_P$1") (pintype "passive"))
      (node (ref "J50") (pin "P$1") (pinfunction "1_P$1") (pintype "passive"))
    )
    (net (code "25") (name "GND") (class "Default")
      (node (ref "C1") (pin "2") (pinfunction "2_2") (pintype "passive"))
      (node (ref "C10") (pin "2") (pinfunction "2_2") (pintype "passive"))
      (node (ref "C11") (pin "2") (pinfunction "2_2") (pintype "passive"))
      (node (ref "C12") (pin "C") (pinfunction "-_C") (pintype "passive"))
      (node (ref "C13") (pin "2") (pinfunction "2_2") (pintype "passive"))
      (node (ref "C15") (pin "2") (pinfunction "2_2") (pintype "passive"))
      (node (ref "C16") (pin "2") (pinfunction "2_2") (pintype "passive"))
      (node (ref "C18") (pin "1") (pinfunction "1_1") (pintype "passive"))
      (node (ref "C2") (pin "2") (pinfunction "2_2") (pintype "passive"))
      (node (ref "C20") (pin "2") (pinfunction "2_2") (pintype "passive"))
      (node (ref "C21") (pin "2") (pinfunction "2_2") (pintype "passive"))
      (node (ref "C22") (pin "2") (pinfunction "2_2") (pintype "passive"))
      (node (ref "C23") (pin "2") (pinfunction "2_2") (pintype "passive"))
      (node (ref "C24") (pin "2") (pinfunction "2_2") (pintype "passive"))
      (node (ref "C25") (pin "2") (pinfunction "2_2") (pintype "passive"))
      (node (ref "C26") (pin "2") (pinfunction "2_2") (pintype "passive"))
      (node (ref "C3") (pin "2") (pinfunction "2_2") (pintype "passive"))
      (node (ref "C4") (pin "2") (pinfunction "2_2") (pintype "passive"))
      (node (ref "C5") (pin "1") (pinfunction "1_1") (pintype "passive"))
      (node (ref "C6") (pin "2") (pinfunction "2_2") (pintype "passive"))
      (node (ref "C7") (pin "2") (pinfunction "2_2") (pintype "passive"))
      (node (ref "C8") (pin "2") (pinfunction "2_2") (pintype "passive"))
      (node (ref "C9") (pin "2") (pinfunction "2_2") (pintype "passive"))
      (node (ref "D2") (pin "3") (pinfunction "VSS_3") (pintype "bidirectional"))
      (node (ref "D31") (pin "3") (pinfunction "VSS_3") (pintype "bidirectional"))
      (node (ref "D32") (pin "3") (pinfunction "VSS_3") (pintype "bidirectional"))
      (node (ref "D33") (pin "3") (pinfunction "VSS_3") (pintype "bidirectional"))
      (node (ref "D5") (pin "3") (pinfunction "VSS_3") (pintype "bidirectional"))
      (node (ref "D6") (pin "3") (pinfunction "VSS_3") (pintype "bidirectional"))
      (node (ref "IC1") (pin "2") (pinfunction "GND_2") (pintype "bidirectional"))
      (node (ref "J11") (pin "P$1") (pinfunction "1_P$1") (pintype "passive"))
      (node (ref "J19") (pin "P$1") (pinfunction "1_P$1") (pintype "passive"))
      (node (ref "J20") (pin "P$1") (pinfunction "1_P$1") (pintype "passive"))
      (node (ref "J27") (pin "P$1") (pinfunction "1_P$1") (pintype "passive"))
      (node (ref "J29") (pin "P$1") (pinfunction "1_P$1") (pintype "passive"))
      (node (ref "J31") (pin "P$1") (pinfunction "1_P$1") (pintype "passive"))
      (node (ref "J33") (pin "P$1") (pinfunction "1_P$1") (pintype "passive"))
      (node (ref "J43") (pin "P$1") (pinfunction "1_P$1") (pintype "passive"))
      (node (ref "J46") (pin "P$1") (pinfunction "1_P$1") (pintype "passive"))
      (node (ref "J49") (pin "P$1") (pinfunction "1_P$1") (pintype "passive"))
      (node (ref "J51") (pin "P$1") (pinfunction "1_P$1") (pintype "passive"))
      (node (ref "J55") (pin "P$1") (pinfunction "1_P$1") (pintype "passive"))
      (node (ref "J58") (pin "P$1") (pinfunction "1_P$1") (pintype "passive"))
      (node (ref "J59") (pin "P$1") (pinfunction "1_P$1") (pintype "passive"))
      (node (ref "J6") (pin "P$1") (pinfunction "1_P$1") (pintype "passive"))
      (node (ref "J61") (pin "P$1") (pinfunction "1_P$1") (pintype "passive"))
      (node (ref "J63") (pin "P$1") (pinfunction "1_P$1") (pintype "passive"))
      (node (ref "J65") (pin "P$1") (pinfunction "1_P$1") (pintype "passive"))
      (node (ref "J67") (pin "P$1") (pinfunction "1_P$1") (pintype "passive"))
      (node (ref "J69") (pin "P$1") (pinfunction "1_P$1") (pintype "passive"))
      (node (ref "J72") (pin "P$1") (pinfunction "1_P$1") (pintype "passive"))
      (node (ref "J75") (pin "P$1") (pinfunction "1_P$1") (pintype "passive"))
      (node (ref "JP3") (pin "GND1") (pinfunction "GND_GND1") (pintype "bidirectional"))
      (node (ref "JP3") (pin "SHIELD1") (pinfunction "SHIELD_SHIELD1") (pintype "bidirectional"))
      (node (ref "JP3") (pin "SHIELD2") (pinfunction "SHIELD_SHIELD2") (pintype "bidirectional"))
      (node (ref "JP3") (pin "SHIELD3") (pinfunction "SHIELD_SHIELD3") (pintype "bidirectional"))
      (node (ref "JP5") (pin "3") (pinfunction "GND_3") (pintype "bidirectional"))
      (node (ref "JP5") (pin "5") (pinfunction "GND_5") (pintype "bidirectional"))
      (node (ref "R11") (pin "1") (pinfunction "1_1") (pintype "passive"))
      (node (ref "R15") (pin "1") (pinfunction "1_1") (pintype "passive"))
      (node (ref "R17") (pin "1") (pinfunction "1_1") (pintype "passive"))
      (node (ref "S1") (pin "1") (pinfunction "1_1") (pintype "passive"))
      (node (ref "S1") (pin "2") (pinfunction "1_2") (pintype "passive"))
      (node (ref "U1") (pin "18") (pinfunction "GND_18") (pintype "bidirectional"))
      (node (ref "U1") (pin "35") (pinfunction "GND_35") (pintype "bidirectional"))
      (node (ref "U1") (pin "42") (pinfunction "GND_42") (pintype "bidirectional"))
      (node (ref "U1") (pin "5") (pinfunction "GNDANA_5") (pintype "bidirectional"))
      (node (ref "U2") (pin "2") (pinfunction "GND_2") (pintype "input"))
      (node (ref "U3") (pin "3") (pinfunction "GND_3") (pintype "bidirectional"))
      (node (ref "U4") (pin "P$8") (pinfunction "GND_P$8") (pintype "bidirectional"))
      (node (ref "U5") (pin "2") (pinfunction "V-_2") (pintype "power_in"))
      (node (ref "U6") (pin "2") (pinfunction "GND_2") (pintype "bidirectional"))
      (node (ref "U6") (pin "4") (pinfunction "GND_4") (pintype "bidirectional"))
      (node (ref "U6") (pin "6") (pinfunction "GND_6") (pintype "bidirectional"))
      (node (ref "U7") (pin "6") (pinfunction "GND_6") (pintype "bidirectional"))
    )
    (net (code "26") (name "ID") (class "Default")
      (node (ref "JP3") (pin "ID1") (pinfunction "USBID_ID1") (pintype "bidirectional"))
      (node (ref "R4") (pin "1") (pinfunction "1_1") (pintype "passive"))
      (node (ref "R5") (pin "2") (pinfunction "2_2") (pintype "passive"))
      (node (ref "U3") (pin "1") (pinfunction "/OE_1") (pintype "bidirectional"))
      (node (ref "U3") (pin "2") (pinfunction "A_2") (pintype "bidirectional"))
    )
    (net (code "27") (name "Net-(C14-Pad1)") (class "Default")
      (node (ref "C14") (pin "1") (pinfunction "1_1") (pintype "passive"))
      (node (ref "R3") (pin "2") (pinfunction "2_2") (pintype "passive"))
    )
    (net (code "28") (name "Net-(C19-Pad2)") (class "Default")
      (node (ref "C19") (pin "2") (pinfunction "2_2") (pintype "passive"))
      (node (ref "R12") (pin "2") (pinfunction "2_2") (pintype "passive"))
    )
    (net (code "29") (name "Net-(D1-PadC)") (class "Default")
      (node (ref "D1") (pin "C") (pinfunction "C_C") (pintype "passive"))
      (node (ref "R15") (pin "2") (pinfunction "2_2") (pintype "passive"))
    )
    (net (code "30") (name "Net-(D2-DO)") (class "Default")
      (node (ref "D2") (pin "2") (pinfunction "DO_2") (pintype "bidirectional"))
      (node (ref "D5") (pin "4") (pinfunction "DI_4") (pintype "bidirectional"))
    )
    (net (code "31") (name "Net-(D3-PadC)") (class "Default")
      (node (ref "D3") (pin "C") (pinfunction "C_C") (pintype "passive"))
      (node (ref "R17") (pin "2") (pinfunction "2_2") (pintype "passive"))
    )
    (net (code "32") (name "Net-(D5-DO)") (class "Default")
      (node (ref "D5") (pin "2") (pinfunction "DO_2") (pintype "bidirectional"))
      (node (ref "D6") (pin "4") (pinfunction "DI_4") (pintype "bidirectional"))
    )
    (net (code "33") (name "Net-(D31-DO)") (class "Default")
      (node (ref "D31") (pin "2") (pinfunction "DO_2") (pintype "bidirectional"))
      (node (ref "D32") (pin "4") (pinfunction "DI_4") (pintype "bidirectional"))
    )
    (net (code "34") (name "Net-(D32-DO)") (class "Default")
      (node (ref "D32") (pin "2") (pinfunction "DO_2") (pintype "bidirectional"))
      (node (ref "D33") (pin "4") (pinfunction "DI_4") (pintype "bidirectional"))
    )
    (net (code "35") (name "Net-(IC1-AUDIO_IN)") (class "Default")
      (node (ref "C14") (pin "2") (pinfunction "2_2") (pintype "passive"))
      (node (ref "IC1") (pin "5") (pinfunction "AUDIO_IN_5") (pintype "input"))
    )
    (net (code "36") (name "Net-(IC1-CG)") (class "Default")
      (node (ref "C10") (pin "1") (pinfunction "1_1") (pintype "passive"))
      (node (ref "IC1") (pin "6") (pinfunction "CG_6") (pintype "bidirectional"))
    )
    (net (code "37") (name "Net-(IC1-CKIN)") (class "Default")
      (node (ref "C11") (pin "1") (pinfunction "1_1") (pintype "passive"))
      (node (ref "IC1") (pin "8") (pinfunction "CKIN_8") (pintype "bidirectional"))
      (node (ref "R2") (pin "1") (pinfunction "1_1") (pintype "passive"))
    )
    (net (code "38") (name "Net-(J21-1)") (class "Default")
      (node (ref "J21") (pin "P$1") (pinfunction "1_P$1") (pintype "passive"))
      (node (ref "J74") (pin "P$1") (pinfunction "1_P$1") (pintype "passive"))
    )
    (net (code "39") (name "Net-(J71-1)") (class "Default")
      (node (ref "J71") (pin "P$1") (pinfunction "1_P$1") (pintype "passive"))
      (node (ref "S2") (pin "3") (pinfunction "S_3") (pintype "passive"))
    )
    (net (code "40") (name "Net-(JP3-VBUS)") (class "Default")
      (node (ref "F1") (pin "1") (pinfunction "1_1") (pintype "bidirectional"))
      (node (ref "JP3") (pin "VBUS1") (pinfunction "VBUS_VBUS1") (pintype "bidirectional"))
    )
    (net (code "41") (name "Net-(Q2-D)") (class "Default")
      (node (ref "F1") (pin "2") (pinfunction "2_2") (pintype "bidirectional"))
      (node (ref "Q2") (pin "3") (pinfunction "D_3") (pintype "passive"))
    )
    (net (code "42") (name "Net-(Q2-G)") (class "Default")
      (node (ref "Q2") (pin "1") (pinfunction "G_1") (pintype "passive"))
      (node (ref "R7") (pin "1") (pinfunction "1_1") (pintype "passive"))
      (node (ref "U3") (pin "4") (pinfunction "Y_4") (pintype "bidirectional"))
    )
    (net (code "43") (name "Net-(U1-PA00(XIN32{slash}SER1:0{slash}TC2:0))") (class "Default")
      (node (ref "C5") (pin "2") (pinfunction "2_2") (pintype "passive"))
      (node (ref "U1") (pin "1") (pinfunction "PA00(XIN32/SER1:0/TC2:0)_1") (pintype "bidirectional"))
      (node (ref "Y1") (pin "P$2") (pinfunction "2_P$2") (pintype "passive"))
    )
    (net (code "44") (name "Net-(U1-PA01(XOUT32{slash}SER1:1{slash}TC2:1))") (class "Default")
      (node (ref "C6") (pin "1") (pinfunction "1_1") (pintype "passive"))
      (node (ref "U1") (pin "2") (pinfunction "PA01(XOUT32/SER1:1/TC2:1)_2") (pintype "bidirectional"))
      (node (ref "Y1") (pin "P$1") (pinfunction "1_P$1") (pintype "passive"))
    )
    (net (code "45") (name "Net-(U1-VDDANA)") (class "Default")
      (node (ref "C3") (pin "1") (pinfunction "1_1") (pintype "passive"))
      (node (ref "L1") (pin "2") (pinfunction "2_2") (pintype "passive"))
      (node (ref "U1") (pin "6") (pinfunction "VDDANA_6") (pintype "bidirectional"))
    )
    (net (code "46") (name "Net-(U1-VDDCORE)") (class "Default")
      (node (ref "C2") (pin "1") (pinfunction "1_1") (pintype "passive"))
      (node (ref "U1") (pin "43") (pinfunction "VDDCORE_43") (pintype "bidirectional"))
    )
    (net (code "47") (name "Net-(U4-OUT+)") (class "Default")
      (node (ref "JP2") (pin "2") (pinfunction "2_2") (pintype "passive"))
      (node (ref "U4") (pin "P$7") (pinfunction "OUT+_P$7") (pintype "bidirectional"))
    )
    (net (code "48") (name "Net-(U4-OUT-)") (class "Default")
      (node (ref "JP2") (pin "1") (pinfunction "1_1") (pintype "passive"))
      (node (ref "U4") (pin "P$9") (pinfunction "OUT-_P$9") (pintype "bidirectional"))
    )
    (net (code "49") (name "Net-(U4-REG)") (class "Default")
      (node (ref "C15") (pin "1") (pinfunction "1_1") (pintype "passive"))
      (node (ref "U4") (pin "P$1") (pinfunction "REG_P$1") (pintype "bidirectional"))
    )
    (net (code "50") (name "Net-(U5-+IN)") (class "Default")
      (node (ref "C20") (pin "1") (pinfunction "1_1") (pintype "passive"))
      (node (ref "R11") (pin "2") (pinfunction "2_2") (pintype "passive"))
      (node (ref "R9") (pin "1") (pinfunction "1_1") (pintype "passive"))
      (node (ref "U5") (pin "3") (pinfunction "+IN_3") (pintype "input"))
    )
    (net (code "51") (name "Net-(U5--IN)") (class "Default")
      (node (ref "C17") (pin "1") (pinfunction "1_1") (pintype "passive"))
      (node (ref "R12") (pin "1") (pinfunction "1_1") (pintype "passive"))
      (node (ref "R13") (pin "2") (pinfunction "2_2") (pintype "passive"))
      (node (ref "U5") (pin "4") (pinfunction "-IN_4") (pintype "input"))
    )
    (net (code "52") (name "Net-(U6-OUT)") (class "Default")
      (node (ref "C19") (pin "1") (pinfunction "1_1") (pintype "passive"))
      (node (ref "U6") (pin "1") (pinfunction "OUT_1") (pintype "bidirectional"))
    )
    (net (code "53") (name "Net-(U7-LDR)") (class "Default")
      (node (ref "U7") (pin "3") (pinfunction "LDR_3") (pintype "bidirectional"))
      (node (ref "U7") (pin "4") (pinfunction "LEDK_4") (pintype "bidirectional"))
    )
    (net (code "54") (name "RX_LED") (class "Default")
      (node (ref "U1") (pin "48") (pinfunction "PB03(AIN11/SER5:1)_48") (pintype "bidirectional"))
    )
    (net (code "55") (name "SCL") (class "Default")
      (node (ref "J13") (pin "P$1") (pinfunction "1_P$1") (pintype "passive"))
      (node (ref "J15") (pin "P$1") (pinfunction "1_P$1") (pintype "passive"))
      (node (ref "J38") (pin "P$1") (pinfunction "1_P$1") (pintype "passive"))
      (node (ref "J4") (pin "P$1") (pinfunction "1_P$1") (pintype "passive"))
      (node (ref "R8") (pin "1") (pinfunction "1_1") (pintype "passive"))
      (node (ref "U1") (pin "32") (pinfunction "PA23(I2C/SER3:0+)_32") (pintype "bidirectional"))
      (node (ref "U4") (pin "P$2") (pinfunction "SCL_P$2") (pintype "bidirectional"))
      (node (ref "U7") (pin "7") (pinfunction "SCL_7") (pintype "bidirectional"))
    )
    (net (code "56") (name "SDA") (class "Default")
      (node (ref "J12") (pin "P$1") (pinfunction "1_P$1") (pintype "passive"))
      (node (ref "J16") (pin "P$1") (pinfunction "1_P$1") (pintype "passive"))
      (node (ref "J2") (pin "P$1") (pinfunction "1_P$1") (pintype "passive"))
      (node (ref "J39") (pin "P$1") (pinfunction "1_P$1") (pintype "passive"))
      (node (ref "R6") (pin "1") (pinfunction "1_1") (pintype "passive"))
      (node (ref "U1") (pin "31") (pinfunction "PA22(I2C/SER3:0+)_31") (pintype "bidirectional"))
      (node (ref "U4") (pin "P$3") (pinfunction "SDA_P$3") (pintype "bidirectional"))
      (node (ref "U7") (pin "1") (pinfunction "SDA_1") (pintype "bidirectional"))
    )
    (net (code "57") (name "SWCLK") (class "Default")
      (node (ref "JP5") (pin "4") (pinfunction "SWDCLK/TCK_4") (pintype "bidirectional"))
      (node (ref "U1") (pin "45") (pinfunction "PA30(SWCLK/SER1:2+)_45") (pintype "bidirectional"))
    )
    (net (code "58") (name "SWDIO") (class "Default")
      (node (ref "JP5") (pin "2") (pinfunction "SWDIO/TMS_2") (pintype "bidirectional"))
      (node (ref "U1") (pin "46") (pinfunction "PA31(SWDIO/SER1:3+)_46") (pintype "bidirectional"))
    )
    (net (code "59") (name "TX_LED") (class "Default")
      (node (ref "U1") (pin "39") (pinfunction "PA27_39") (pintype "bidirectional"))
    )
    (net (code "60") (name "USB_D+") (class "Default")
      (node (ref "JP3") (pin "D+1") (pinfunction "D+_D+1") (pintype "bidirectional"))
      (node (ref "U1") (pin "34") (pinfunction "PA25(SER3:3+)_34") (pintype "bidirectional"))
    )
    (net (code "61") (name "USB_D-") (class "Default")
      (node (ref "JP3") (pin "D-1") (pinfunction "D-_D-1") (pintype "bidirectional"))
      (node (ref "U1") (pin "33") (pinfunction "PA24(SER3:2+)_33") (pintype "bidirectional"))
    )
    (net (code "62") (name "USB_HOST_EN") (class "Default")
      (node (ref "R5") (pin "1") (pinfunction "1_1") (pintype "passive"))
      (node (ref "U1") (pin "41") (pinfunction "PA28_41") (pintype "bidirectional"))
    )
    (net (code "63") (name "VIN") (class "Default")
      (node (ref "C7") (pin "1") (pinfunction "1_1") (pintype "passive"))
      (node (ref "Q2") (pin "2") (pinfunction "S_2") (pintype "passive"))
      (node (ref "R4") (pin "2") (pinfunction "2_2") (pintype "passive"))
      (node (ref "R7") (pin "2") (pinfunction "2_2") (pintype "passive"))
      (node (ref "S2") (pin "2") (pinfunction "P_2") (pintype "passive"))
      (node (ref "U2") (pin "1") (pinfunction "IN_1") (pintype "input"))
      (node (ref "U2") (pin "3") (pinfunction "EN_3") (pintype "input"))
      (node (ref "U3") (pin "5") (pinfunction "VCC_5") (pintype "bidirectional"))
    )
    (net (code "64") (name "unconnected-(JP5-GNDDTCT-Pad9)") (class "Default")
      (node (ref "JP5") (pin "9") (pinfunction "GNDDTCT_9") (pintype "bidirectional"))
    )
    (net (code "65") (name "unconnected-(JP5-KEY-Pad7)") (class "Default")
      (node (ref "JP5") (pin "7") (pinfunction "KEY_7") (pintype "bidirectional"))
    )
    (net (code "66") (name "unconnected-(JP5-NC{slash}TDI-Pad8)") (class "Default")
      (node (ref "JP5") (pin "8") (pinfunction "NC/TDI_8") (pintype "bidirectional"))
    )
    (net (code "67") (name "unconnected-(JP5-SWO{slash}TDO-Pad6)") (class "Default")
      (node (ref "JP5") (pin "6") (pinfunction "SWO/TDO_6") (pintype "bidirectional"))
    )
    (net (code "68") (name "unconnected-(S2-O-Pad1)") (class "Default")
      (node (ref "S2") (pin "1") (pinfunction "O_1") (pintype "passive"))
    )
    (net (code "69") (name "unconnected-(U1-PA05(AIN5{slash}SER0:1{slash}TC0:1)-Pad10)") (class "Default")
      (node (ref "U1") (pin "10") (pinfunction "PA05(AIN5/SER0:1/TC0:1)_10") (pintype "bidirectional"))
    )
    (net (code "70") (name "unconnected-(U1-PA12(I2C{slash}SER2:0+)-Pad21)") (class "Default")
      (node (ref "U1") (pin "21") (pinfunction "PA12(I2C/SER2:0+)_21") (pintype "bidirectional"))
    )
    (net (code "71") (name "unconnected-(U1-PA13(I2C{slash}SER2:1+)-Pad22)") (class "Default")
      (node (ref "U1") (pin "22") (pinfunction "PA13(I2C/SER2:1+)_22") (pintype "bidirectional"))
    )
    (net (code "72") (name "unconnected-(U1-PB02(AIN10{slash}SER5:0)-Pad47)") (class "Default")
      (node (ref "U1") (pin "47") (pinfunction "PB02(AIN10/SER5:0)_47") (pintype "bidirectional"))
    )
    (net (code "73") (name "unconnected-(U1-PB10(SER4:2+)-Pad19)") (class "Default")
      (node (ref "U1") (pin "19") (pinfunction "PB10(SER4:2+)_19") (pintype "bidirectional"))
    )
    (net (code "74") (name "unconnected-(U1-PB11(SER4:3+)-Pad20)") (class "Default")
      (node (ref "U1") (pin "20") (pinfunction "PB11(SER4:3+)_20") (pintype "bidirectional"))
    )
    (net (code "75") (name "unconnected-(U1-PB22(SER5:2+)-Pad37)") (class "Default")
      (node (ref "U1") (pin "37") (pinfunction "PB22(SER5:2+)_37") (pintype "bidirectional"))
    )
    (net (code "76") (name "unconnected-(U1-PB23(SER5:3+)-Pad38)") (class "Default")
      (node (ref "U1") (pin "38") (pinfunction "PB23(SER5:3+)_38") (pintype "bidirectional"))
    )
    (net (code "77") (name "unconnected-(U2-NC-Pad4)") (class "Default")
      (node (ref "U2") (pin "4") (pinfunction "NC_4") (pintype "input"))
    )
  )
)
